# BT-2.net
KiCad netlist of a schematic drawn in EAGLE
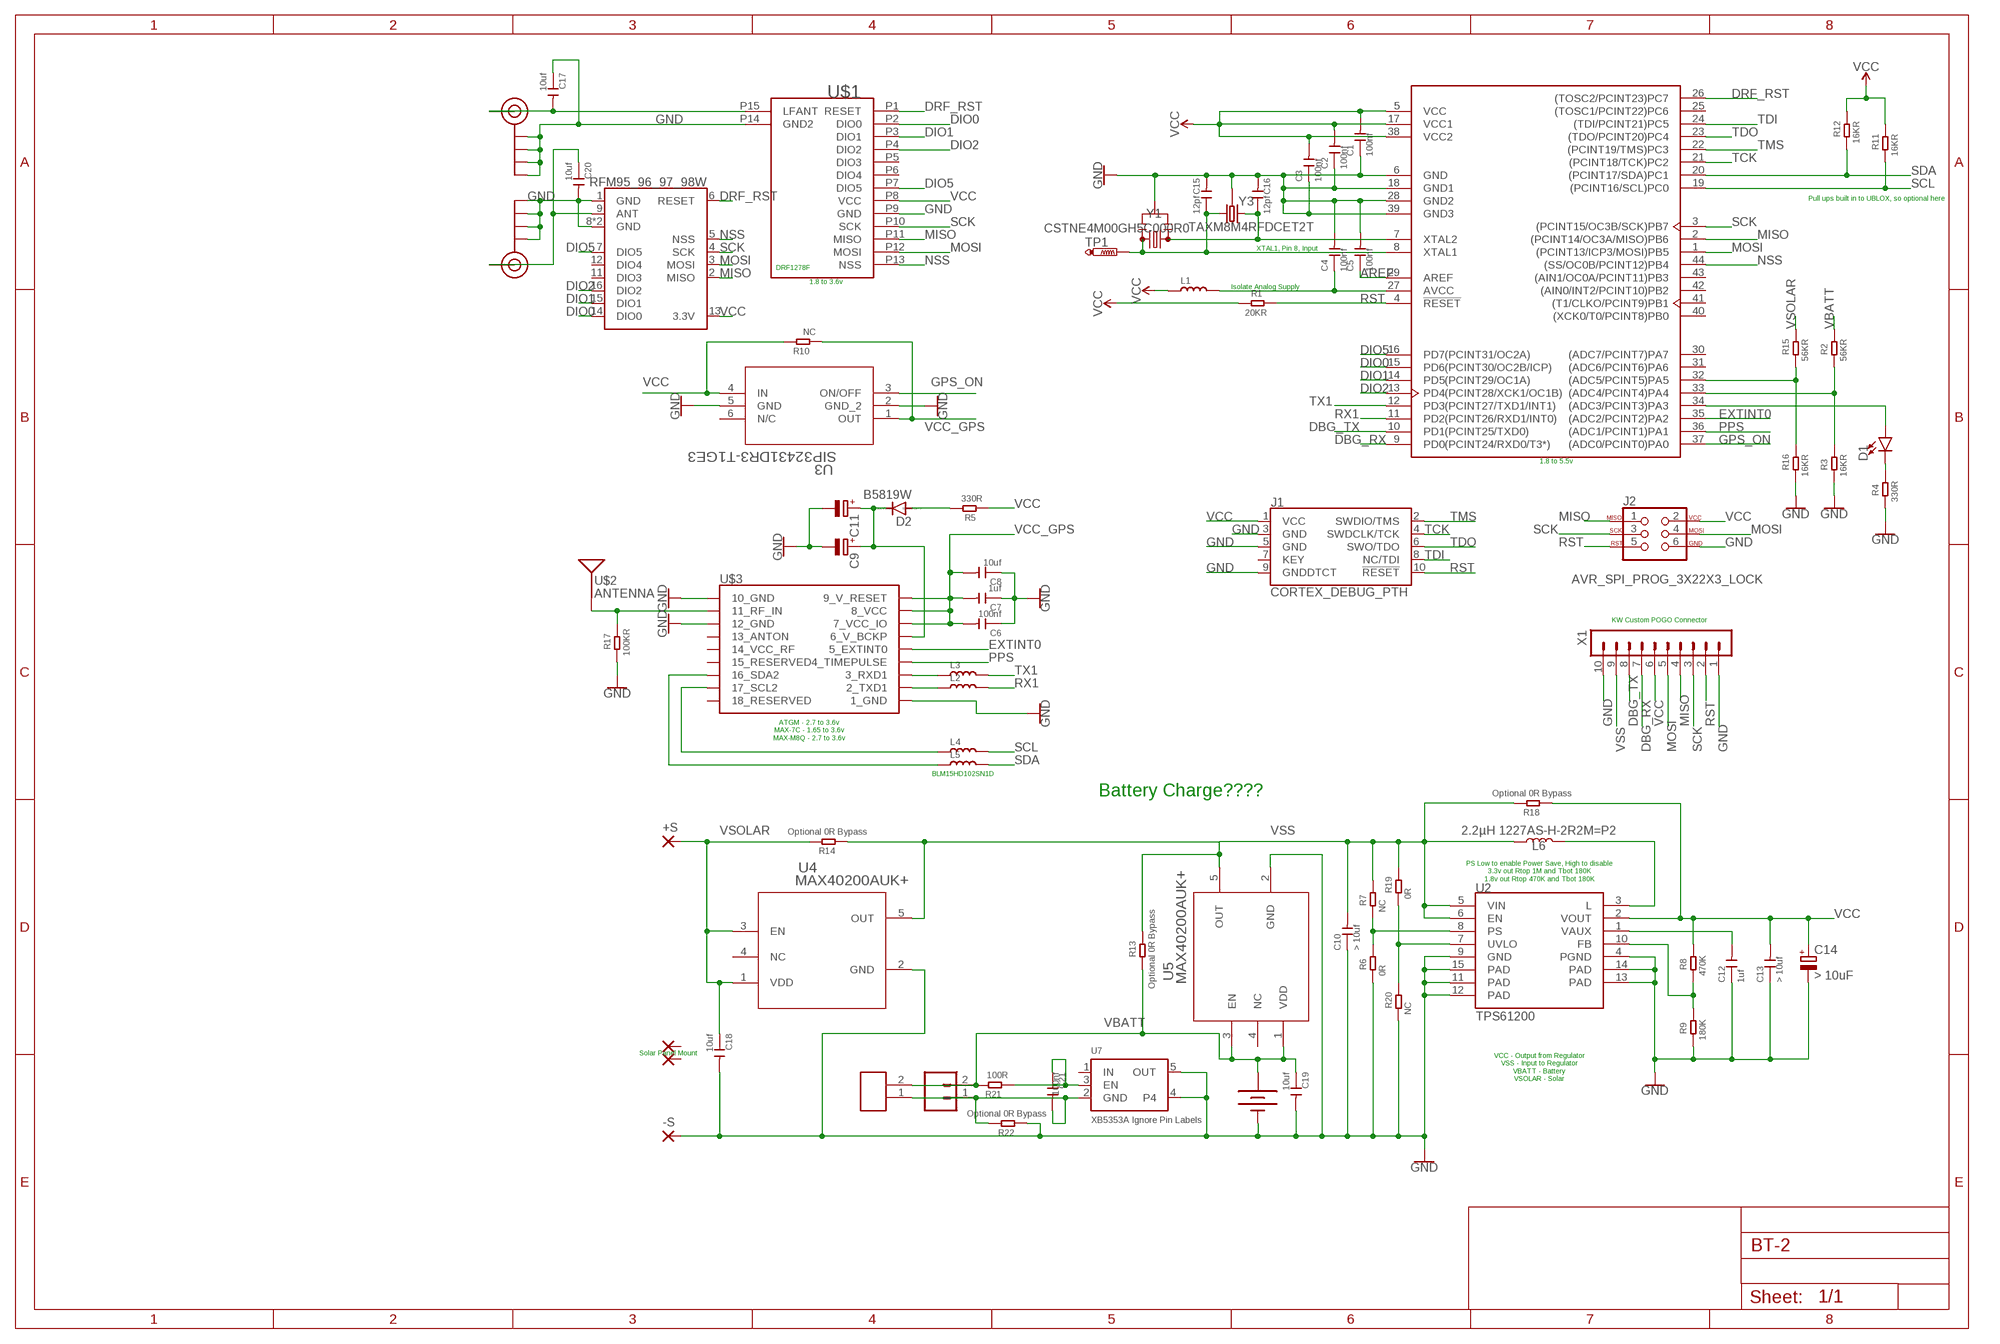
[diagram p0: schematic, sheet 1]

(export (version "E")
  (design (tool "Eeschema 10.0.6"))
  (components
    (comp (ref "+S")
      (value "SMD2")
      (footprint "eagle-import:SMD1,27-2,54")
      (libsource (lib "eagle-import") (part "SMD2"))
    )
    (comp (ref "-S")
      (value "SMD2")
      (footprint "eagle-import:SMD1,27-2,54")
      (libsource (lib "eagle-import") (part "SMD2"))
    )
    (comp (ref "BT1")
      (value "BATTERY")
      (footprint "eagle-import:BATTERY-AA-AAA")
      (libsource (lib "eagle-import") (part "BATTERY"))
    )
    (comp (ref "C1")
      (value "100nf")
      (footprint "eagle-import:C0402")
      (fields (field (name "MPN") "CC0402KRX7R8BB104"))
      (libsource (lib "eagle-import") (part "CERAMIC-100NF-25V-10%-X7R(0402)"))
    )
    (comp (ref "C2")
      (value "100nf")
      (footprint "eagle-import:C0402")
      (fields (field (name "MPN") "CC0402KRX7R8BB104"))
      (libsource (lib "eagle-import") (part "CERAMIC-100NF-25V-10%-X7R(0402)"))
    )
    (comp (ref "C3")
      (value "100nf")
      (footprint "eagle-import:C0402")
      (fields (field (name "MPN") "CC0402KRX7R8BB104"))
      (libsource (lib "eagle-import") (part "CERAMIC-100NF-25V-10%-X7R(0402)"))
    )
    (comp (ref "C4")
      (value "100nf")
      (footprint "eagle-import:C0402")
      (fields (field (name "MPN") "CC0402KRX7R8BB104"))
      (libsource (lib "eagle-import") (part "CERAMIC-100NF-25V-10%-X7R(0402)"))
    )
    (comp (ref "C5")
      (value "100nf")
      (footprint "eagle-import:C0402")
      (fields (field (name "MPN") "CC0402KRX7R8BB104"))
      (libsource (lib "eagle-import") (part "CERAMIC-100NF-25V-10%-X7R(0402)"))
    )
    (comp (ref "C6")
      (value "100nf")
      (footprint "eagle-import:C0402")
      (fields (field (name "MPN") "CC0402KRX7R8BB104"))
      (libsource (lib "eagle-import") (part "CERAMIC-100NF-25V-10%-X7R(0402)"))
    )
    (comp (ref "C7")
      (value "1uf")
      (footprint "eagle-import:C0402")
      (fields (field (name "MPN") "CC0402KRX5R6BB105"))
      (libsource (lib "eagle-import") (part "CERAMIC-1UF-10V-10%-X5R(0402)"))
    )
    (comp (ref "C8")
      (value "10uf")
      (footprint "eagle-import:C0402")
      (fields (field (name "MPN") "CC0402MRX5R5BB106"))
      (libsource (lib "eagle-import") (part "CERAMIC-10UF-6.3V-20%-X5R(0402)"))
    )
    (comp (ref "C9")
      (value "RCL_CPOL-EUSMCC")
      (footprint "eagle-import:RCL_SMC_C")
      (libsource (lib "eagle-import") (part "RCL_CPOL-EUSMCC"))
    )
    (comp (ref "C10")
      (value "> 10uf")
      (footprint "eagle-import:C0603")
      (fields (field (name "MPN") "CC0603KRX5R6BB106"))
      (libsource (lib "eagle-import") (part "CERAMIC-10UF-10V-10%-X5R(0603)"))
    )
    (comp (ref "C11")
      (value "C-POL_ECAP-10.5MM")
      (footprint "eagle-import:CAPAE1030X1050N")
      (libsource (lib "eagle-import") (part "C-POLECAP-10.5MM_"))
    )
    (comp (ref "C12")
      (value "1uf")
      (footprint "eagle-import:C0402")
      (fields (field (name "MPN") "CC0402KRX5R6BB105"))
      (libsource (lib "eagle-import") (part "CERAMIC-1UF-10V-10%-X5R(0402)"))
    )
    (comp (ref "C13")
      (value "> 10uf")
      (footprint "eagle-import:C0603")
      (fields (field (name "MPN") "CC0603KRX5R6BB106"))
      (libsource (lib "eagle-import") (part "CERAMIC-10UF-10V-10%-X5R(0603)"))
    )
    (comp (ref "C14")
      (value "> 10uF")
      (footprint "eagle-import:RCL_SMC_C")
      (libsource (lib "eagle-import") (part "RCL_CPOL-EUSMCC"))
    )
    (comp (ref "C15")
      (value "12pf")
      (footprint "eagle-import:C0402")
      (fields (field (name "MPN") "CC0402KRX7R8BB104"))
      (libsource (lib "eagle-import") (part "CERAMIC-100NF-25V-10%-X7R(0402)"))
    )
    (comp (ref "C16")
      (value "12pf")
      (footprint "eagle-import:C0402")
      (fields (field (name "MPN") "CC0402KRX7R8BB104"))
      (libsource (lib "eagle-import") (part "CERAMIC-100NF-25V-10%-X7R(0402)"))
    )
    (comp (ref "C17")
      (value "10uf")
      (footprint "eagle-import:C0402")
      (fields (field (name "MPN") "CC0402MRX5R5BB106"))
      (libsource (lib "eagle-import") (part "CERAMIC-10UF-6.3V-20%-X5R(0402)"))
    )
    (comp (ref "C18")
      (value "10uf")
      (footprint "eagle-import:C0402")
      (fields (field (name "MPN") "CC0402MRX5R5BB106"))
      (libsource (lib "eagle-import") (part "CERAMIC-10UF-6.3V-20%-X5R(0402)"))
    )
    (comp (ref "C19")
      (value "10uf")
      (footprint "eagle-import:C0402")
      (fields (field (name "MPN") "CC0402MRX5R5BB106"))
      (libsource (lib "eagle-import") (part "CERAMIC-10UF-6.3V-20%-X5R(0402)"))
    )
    (comp (ref "C20")
      (value "10uf")
      (footprint "eagle-import:C0402")
      (fields (field (name "MPN") "CC0402MRX5R5BB106"))
      (libsource (lib "eagle-import") (part "CERAMIC-10UF-6.3V-20%-X5R(0402)"))
    )
    (comp (ref "C21")
      (value "100nf")
      (footprint "eagle-import:C0402")
      (fields (field (name "MPN") "CC0402KRX7R8BB104"))
      (libsource (lib "eagle-import") (part "CERAMIC-100NF-25V-10%-X7R(0402)"))
    )
    (comp (ref "D1")
      (value "LED0603")
      (footprint "eagle-import:LED-0603")
      (libsource (lib "eagle-import") (part "LED0603"))
    )
    (comp (ref "D2")
      (value "B5819W")
      (footprint "eagle-import:SOD123")
      (libsource (lib "eagle-import") (part "DIODE-SOD123"))
    )
    (comp (ref "J$1")
      (value "SMA_EDGE")
      (footprint "eagle-import:SMA-EDGE")
      (libsource (lib "eagle-import") (part "SMA_EDGE"))
    )
    (comp (ref "J$2")
      (value "SMA_EDGE")
      (footprint "eagle-import:SMA-EDGE")
      (libsource (lib "eagle-import") (part "SMA_EDGE"))
    )
    (comp (ref "J1")
      (value "CORTEX_DEBUG_PTH")
      (footprint "eagle-import:2X5-PTH-1.27MM")
      (libsource (lib "eagle-import") (part "CORTEX_DEBUG_PTH"))
    )
    (comp (ref "J2")
      (value "AVR_SPI_PROG_3X22X3_LOCK")
      (footprint "eagle-import:2X3_LOCK")
      (libsource (lib "eagle-import") (part "AVR_SPI_PROG_3X22X3_LOCK"))
    )
    (comp (ref "J3")
      (value "JST_ZH_2PIN")
      (footprint "eagle-import:JST_ZH_2PIN")
      (libsource (lib "eagle-import") (part "JST_ZH_2PIN"))
    )
    (comp (ref "J4")
      (value "CONN_02JST-PTH-2-KIT")
      (footprint "eagle-import:JST-2-PTH-KIT")
      (libsource (lib "eagle-import") (part "CONN_02JST-PTH-2-KIT"))
    )
    (comp (ref "L1")
      (value "BLM15HD102SN1D")
      (footprint "eagle-import:L0402")
      (libsource (lib "eagle-import") (part "SMD-INDUCTOR-3.3NH-0.3NH-300MA(0402)"))
    )
    (comp (ref "L2")
      (value "BLM15HD102SN1D")
      (footprint "eagle-import:L0402")
      (libsource (lib "eagle-import") (part "SMD-INDUCTOR-3.3NH-0.3NH-300MA(0402)"))
    )
    (comp (ref "L3")
      (value "BLM15HD102SN1D")
      (footprint "eagle-import:L0402")
      (libsource (lib "eagle-import") (part "SMD-INDUCTOR-3.3NH-0.3NH-300MA(0402)"))
    )
    (comp (ref "L4")
      (value "BLM15HD102SN1D")
      (footprint "eagle-import:L0402")
      (libsource (lib "eagle-import") (part "SMD-INDUCTOR-3.3NH-0.3NH-300MA(0402)"))
    )
    (comp (ref "L5")
      (value "BLM15HD102SN1D")
      (footprint "eagle-import:L0402")
      (libsource (lib "eagle-import") (part "SMD-INDUCTOR-3.3NH-0.3NH-300MA(0402)"))
    )
    (comp (ref "L6")
      (value "2.2µH 1227AS-H-2R2M=P2")
      (footprint "eagle-import:INDUCTOR_4.7UH")
      (libsource (lib "eagle-import") (part "INDUCTOR-CDRH-4.7UH"))
    )
    (comp (ref "NC1")
      (value "SMD2")
      (footprint "eagle-import:SMD1,27-2,54")
      (libsource (lib "eagle-import") (part "SMD2"))
    )
    (comp (ref "NC2")
      (value "SMD2")
      (footprint "eagle-import:SMD1,27-2,54")
      (libsource (lib "eagle-import") (part "SMD2"))
    )
    (comp (ref "R1")
      (value "20KR")
      (footprint "eagle-import:R0402")
      (fields (field (name "MPN") "RC0402JR-070RL"))
      (libsource (lib "eagle-import") (part "SMD-RES-20K-5%-1/16W(0402)"))
    )
    (comp (ref "R2")
      (value "56KR")
      (footprint "eagle-import:R0402")
      (fields (field (name "MPN") "RC0402JR-070RL"))
      (libsource (lib "eagle-import") (part "SMD-RES-20K-5%-1/16W(0402)"))
    )
    (comp (ref "R3")
      (value "16KR")
      (footprint "eagle-import:R0402")
      (fields (field (name "MPN") "RC0402JR-070RL"))
      (libsource (lib "eagle-import") (part "SMD-RES-20K-5%-1/16W(0402)"))
    )
    (comp (ref "R4")
      (value "330R")
      (footprint "eagle-import:R0402")
      (fields (field (name "MPN") "RC0402JR-070RL"))
      (libsource (lib "eagle-import") (part "SMD-RES-20K-5%-1/16W(0402)"))
    )
    (comp (ref "R5")
      (value "330R")
      (footprint "eagle-import:R0402")
      (fields (field (name "MPN") "RC0402JR-070RL"))
      (libsource (lib "eagle-import") (part "SMD-RES-20K-5%-1/16W(0402)"))
    )
    (comp (ref "R6")
      (value "0R")
      (footprint "eagle-import:R0402")
      (fields (field (name "MPN") "RC0402JR-070RL"))
      (libsource (lib "eagle-import") (part "SMD-RES-20K-5%-1/16W(0402)"))
    )
    (comp (ref "R7")
      (value "NC")
      (footprint "eagle-import:R0402")
      (fields (field (name "MPN") "RC0402JR-070RL"))
      (libsource (lib "eagle-import") (part "SMD-RES-20K-5%-1/16W(0402)"))
    )
    (comp (ref "R8")
      (value "470K")
      (footprint "eagle-import:R0402")
      (fields (field (name "MPN") "RC0402JR-070RL"))
      (libsource (lib "eagle-import") (part "SMD-RES-20K-5%-1/16W(0402)"))
    )
    (comp (ref "R9")
      (value "180K")
      (footprint "eagle-import:R0402")
      (fields (field (name "MPN") "RC0402JR-070RL"))
      (libsource (lib "eagle-import") (part "SMD-RES-20K-5%-1/16W(0402)"))
    )
    (comp (ref "R10")
      (value "NC")
      (footprint "eagle-import:R0402")
      (fields (field (name "MPN") "RC0402JR-070RL"))
      (libsource (lib "eagle-import") (part "SMD-RES-20K-5%-1/16W(0402)"))
    )
    (comp (ref "R11")
      (value "16KR")
      (footprint "eagle-import:R0402")
      (fields (field (name "MPN") "RC0402JR-070RL"))
      (libsource (lib "eagle-import") (part "SMD-RES-20K-5%-1/16W(0402)"))
    )
    (comp (ref "R12")
      (value "16KR")
      (footprint "eagle-import:R0402")
      (fields (field (name "MPN") "RC0402JR-070RL"))
      (libsource (lib "eagle-import") (part "SMD-RES-20K-5%-1/16W(0402)"))
    )
    (comp (ref "R13")
      (value "Optional 0R Bypass")
      (footprint "eagle-import:R0402")
      (fields (field (name "MPN") "RC0402JR-070RL"))
      (libsource (lib "eagle-import") (part "SMD-RES-20K-5%-1/16W(0402)"))
    )
    (comp (ref "R14")
      (value "Optional 0R Bypass")
      (footprint "eagle-import:R0402")
      (fields (field (name "MPN") "RC0402JR-070RL"))
      (libsource (lib "eagle-import") (part "SMD-RES-20K-5%-1/16W(0402)"))
    )
    (comp (ref "R15")
      (value "56KR")
      (footprint "eagle-import:R0402")
      (fields (field (name "MPN") "RC0402JR-070RL"))
      (libsource (lib "eagle-import") (part "SMD-RES-20K-5%-1/16W(0402)"))
    )
    (comp (ref "R16")
      (value "16KR")
      (footprint "eagle-import:R0402")
      (fields (field (name "MPN") "RC0402JR-070RL"))
      (libsource (lib "eagle-import") (part "SMD-RES-20K-5%-1/16W(0402)"))
    )
    (comp (ref "R17")
      (value "100KR")
      (footprint "eagle-import:R0402")
      (fields (field (name "MPN") "RC0402JR-070RL"))
      (libsource (lib "eagle-import") (part "SMD-RES-20K-5%-1/16W(0402)"))
    )
    (comp (ref "R18")
      (value "Optional 0R Bypass")
      (footprint "eagle-import:R0402")
      (fields (field (name "MPN") "RC0402JR-070RL"))
      (libsource (lib "eagle-import") (part "SMD-RES-20K-5%-1/16W(0402)"))
    )
    (comp (ref "R19")
      (value "0R")
      (footprint "eagle-import:R0402")
      (fields (field (name "MPN") "RC0402JR-070RL"))
      (libsource (lib "eagle-import") (part "SMD-RES-20K-5%-1/16W(0402)"))
    )
    (comp (ref "R20")
      (value "NC")
      (footprint "eagle-import:R0402")
      (fields (field (name "MPN") "RC0402JR-070RL"))
      (libsource (lib "eagle-import") (part "SMD-RES-20K-5%-1/16W(0402)"))
    )
    (comp (ref "R21")
      (value "100R")
      (footprint "eagle-import:R0402")
      (fields (field (name "MPN") "RC0402JR-070RL"))
      (libsource (lib "eagle-import") (part "SMD-RES-20K-5%-1/16W(0402)"))
    )
    (comp (ref "R22")
      (value "Optional 0R Bypass")
      (footprint "eagle-import:R0402")
      (fields (field (name "MPN") "RC0402JR-070RL"))
      (libsource (lib "eagle-import") (part "SMD-RES-20K-5%-1/16W(0402)"))
    )
    (comp (ref "TP1")
      (value "TESTPAD_PTR1TP10R")
      (footprint "eagle-import:TESTPAD_TP10R")
      (libsource (lib "eagle-import") (part "TESTPAD_PTR1TP10R"))
    )
    (comp (ref "U$1")
      (value "DRF1278F_2NO_PINS")
      (footprint "eagle-import:DRF1278F_2_NO_PINS")
      (libsource (lib "eagle-import") (part "DRF1278F_2NO_PINS"))
    )
    (comp (ref "U$2")
      (value "ANTENNA")
      (footprint "eagle-import:ANT-GPS-3X10MM")
      (libsource (lib "eagle-import") (part "ANTENNA"))
    )
    (comp (ref "U$3")
      (value "AVA_UBLOX_MAX-6")
      (footprint "eagle-import:AVA_UBLOX_MAX-6")
      (libsource (lib "eagle-import") (part "AVA_UBLOX_MAX-6"))
    )
    (comp (ref "U1")
      (value "ATMEGA1284P-AU")
      (footprint "eagle-import:TQFP-44")
      (fields
        (field (name "DIGIKEY_PART_NUMBER") "ATMEGA1284P-AU-ND")
        (field (name "MANUFACTURER") "Microchip Technology")
        (field (name "CREATED_BY") "PCBLayout.com")
      )
      (libsource (lib "eagle-import") (part "ATMEGA1284P-AU"))
    )
    (comp (ref "U2")
      (value "TPS61200")
      (footprint "eagle-import:QFN-10_PAD")
      (libsource (lib "eagle-import") (part "TPS61200"))
    )
    (comp (ref "U3")
      (value "SIP32431DR3-T1GE3")
      (footprint "eagle-import:SC-70-6_VIS")
      (fields (field (name "COPYRIGHT") "Copyright (C) 2018 Accelerated Designs. All rights reserved"))
      (libsource (lib "eagle-import") (part "SIP32431DR3-T1GE3"))
    )
    (comp (ref "U4")
      (value "MAX40200AUK+")
      (footprint "eagle-import:RAJX_V4.5_REVA_21-0057F_MXM")
      (fields (field (name "COPYRIGHT") "Copyright (C) 2018 Accelerated Designs. All rights reserved"))
      (libsource (lib "eagle-import") (part "RAJX_V4.5_REVA_MAX40200AUK+"))
    )
    (comp (ref "U5")
      (value "MAX40200AUK+")
      (footprint "eagle-import:RAJX_V4.5_REVA_21-0057F_MXM")
      (fields (field (name "COPYRIGHT") "Copyright (C) 2018 Accelerated Designs. All rights reserved"))
      (libsource (lib "eagle-import") (part "RAJX_V4.5_REVA_MAX40200AUK+"))
    )
    (comp (ref "U6")
      (value "RFM95_96_97_98W")
      (footprint "eagle-import:RFM69HCW-XXXS2")
      (libsource (lib "eagle-import") (part "RFM69HCW-433"))
    )
    (comp (ref "U7")
      (value "XB5353A Ignore Pin Labels")
      (footprint "eagle-import:SOT23-5_1")
      (libsource (lib "eagle-import") (part "VREG_SOT23-5"))
    )
    (comp (ref "X1")
      (value "KEW_HF_V13_M_1R10KW_50MIL-H")
      (footprint "eagle-import:KEW_HF_V13_M_1R09_50MIL-H")
      (libsource (lib "eagle-import") (part "KEW_HF_V13_M_1R10KW_50MIL-H"))
    )
    (comp (ref "Y1")
      (value "CSTNE4M00GH5C000R0")
      (footprint "eagle-import:SPARKFUN-CLOCKS-KW_RESONATOR-SMD-3.2X1.3")
      (libsource (lib "eagle-import") (part "SPARKFUN-CLOCKS-KW_RESONATOR-8MHZSMD_3.2X1.3"))
    )
    (comp (ref "Y3")
      (value "TAXM8M4RFDCET2T")
      (footprint "eagle-import:CRYSTAL-SMD-3.2X2.5MM")
      (libsource (lib "eagle-import") (part "CRYSTAL-GROUNDEDSMD-3.2X2.5"))
    )
  )
  (nets
    (net (code "1") (name "/AREF") (class "Default")
      (node (ref "C5") (pin "1") (pinfunction "1_1") (pintype "passive"))
      (node (ref "U1") (pin "29") (pinfunction "AREF_29") (pintype "input"))
    )
    (net (code "2") (name "/DBG_RX") (class "Default")
      (node (ref "U1") (pin "9") (pinfunction "PD0(PCINT24/RXD0/T3*)_9") (pintype "bidirectional"))
      (node (ref "X1") (pin "7") (pinfunction "7_7") (pintype "bidirectional"))
    )
    (net (code "3") (name "/DBG_TX") (class "Default")
      (node (ref "U1") (pin "10") (pinfunction "PD1(PCINT25/TXD0)_10") (pintype "bidirectional"))
      (node (ref "X1") (pin "8") (pinfunction "8_8") (pintype "bidirectional"))
    )
    (net (code "4") (name "/DIO0") (class "Default")
      (node (ref "U$1") (pin "P2") (pinfunction "DIO0_P2") (pintype "bidirectional"))
      (node (ref "U1") (pin "15") (pinfunction "PD6(PCINT30/OC2B/ICP)_15") (pintype "bidirectional"))
      (node (ref "U6") (pin "14") (pinfunction "DIO0_14") (pintype "bidirectional"))
    )
    (net (code "5") (name "/DIO1") (class "Default")
      (node (ref "U$1") (pin "P3") (pinfunction "DIO1_P3") (pintype "bidirectional"))
      (node (ref "U1") (pin "14") (pinfunction "PD5(PCINT29/OC1A)_14") (pintype "bidirectional"))
      (node (ref "U6") (pin "15") (pinfunction "DIO1_15") (pintype "bidirectional"))
    )
    (net (code "6") (name "/DIO2") (class "Default")
      (node (ref "U$1") (pin "P4") (pinfunction "DIO2_P4") (pintype "bidirectional"))
      (node (ref "U1") (pin "13") (pinfunction "PD4(PCINT28/XCK1/OC1B)_13") (pintype "bidirectional"))
      (node (ref "U6") (pin "16") (pinfunction "DIO2_16") (pintype "bidirectional"))
    )
    (net (code "7") (name "/DIO5") (class "Default")
      (node (ref "U$1") (pin "P7") (pinfunction "DIO5_P7") (pintype "bidirectional"))
      (node (ref "U1") (pin "16") (pinfunction "PD7(PCINT31/OC2A)_16") (pintype "bidirectional"))
      (node (ref "U6") (pin "7") (pinfunction "DIO5_7") (pintype "bidirectional"))
    )
    (net (code "8") (name "/DRF_RST") (class "Default")
      (node (ref "U$1") (pin "P1") (pinfunction "RESET_P1") (pintype "bidirectional"))
      (node (ref "U1") (pin "26") (pinfunction "(TOSC2/PCINT23)PC7_26") (pintype "bidirectional"))
      (node (ref "U6") (pin "6") (pinfunction "RESET_6") (pintype "input"))
    )
    (net (code "9") (name "/EXTINT0") (class "Default")
      (node (ref "U$3") (pin "5_EXTINT0") (pinfunction "5_EXTINT0_5_EXTINT0") (pintype "bidirectional"))
      (node (ref "U1") (pin "35") (pinfunction "(ADC2/PCINT2)PA2_35") (pintype "bidirectional"))
    )
    (net (code "10") (name "/GPS_ON") (class "Default")
      (node (ref "U1") (pin "37") (pinfunction "(ADC0/PCINT0)PA0_37") (pintype "bidirectional"))
      (node (ref "U3") (pin "3") (pinfunction "ON/OFF_3") (pintype "passive"))
    )
    (net (code "11") (name "/IN") (class "Default")
      (node (ref "U7") (pin "1") (pinfunction "IN_1") (pintype "power_in"))
    )
    (net (code "12") (name "/MISO") (class "Default")
      (node (ref "J2") (pin "1") (pinfunction "1_1") (pintype "passive"))
      (node (ref "U$1") (pin "P11") (pinfunction "MISO_P11") (pintype "bidirectional"))
      (node (ref "U1") (pin "2") (pinfunction "(PCINT14/OC3A/MISO)PB6_2") (pintype "bidirectional"))
      (node (ref "U6") (pin "2") (pinfunction "MISO_2") (pintype "bidirectional"))
      (node (ref "X1") (pin "4") (pinfunction "4_4") (pintype "bidirectional"))
    )
    (net (code "13") (name "/MOSI") (class "Default")
      (node (ref "J2") (pin "4") (pinfunction "4_4") (pintype "passive"))
      (node (ref "U$1") (pin "P12") (pinfunction "MOSI_P12") (pintype "bidirectional"))
      (node (ref "U1") (pin "1") (pinfunction "(PCINT13/ICP3/MOSI)PB5_1") (pintype "bidirectional"))
      (node (ref "U6") (pin "3") (pinfunction "MOSI_3") (pintype "input"))
      (node (ref "X1") (pin "5") (pinfunction "5_5") (pintype "bidirectional"))
    )
    (net (code "14") (name "/NSS") (class "Default")
      (node (ref "U$1") (pin "P13") (pinfunction "NSS_P13") (pintype "bidirectional"))
      (node (ref "U1") (pin "44") (pinfunction "(SS/OC0B/PCINT12)PB4_44") (pintype "bidirectional"))
      (node (ref "U6") (pin "5") (pinfunction "NSS_5") (pintype "input"))
    )
    (net (code "15") (name "/PPS") (class "Default")
      (node (ref "U$3") (pin "4_TIMEPULSE") (pinfunction "4_TIMEPULSE_4_TIMEPULSE") (pintype "bidirectional"))
      (node (ref "U1") (pin "36") (pinfunction "(ADC1/PCINT1)PA1_36") (pintype "bidirectional"))
    )
    (net (code "16") (name "/RST") (class "Default")
      (node (ref "J1") (pin "10") (pinfunction "~{RESET}_10") (pintype "bidirectional"))
      (node (ref "J2") (pin "5") (pinfunction "5_5") (pintype "passive"))
      (node (ref "R1") (pin "2") (pinfunction "2_2") (pintype "passive"))
      (node (ref "U1") (pin "4") (pinfunction "~{RESET}_4") (pintype "input"))
      (node (ref "X1") (pin "2") (pinfunction "2_2") (pintype "bidirectional"))
    )
    (net (code "17") (name "/RX1") (class "Default")
      (node (ref "L2") (pin "2") (pinfunction "2_2") (pintype "passive"))
      (node (ref "U1") (pin "11") (pinfunction "PD2(PCINT26/RXD1/INT0)_11") (pintype "bidirectional"))
    )
    (net (code "18") (name "/SCK") (class "Default")
      (node (ref "J2") (pin "3") (pinfunction "3_3") (pintype "passive"))
      (node (ref "U$1") (pin "P10") (pinfunction "SCK_P10") (pintype "bidirectional"))
      (node (ref "U1") (pin "3") (pinfunction "(PCINT15/OC3B/SCK)PB7_3") (pintype "bidirectional"))
      (node (ref "U6") (pin "4") (pinfunction "SCK_4") (pintype "input"))
      (node (ref "X1") (pin "3") (pinfunction "3_3") (pintype "bidirectional"))
    )
    (net (code "19") (name "/SCL") (class "Default")
      (node (ref "L4") (pin "2") (pinfunction "2_2") (pintype "passive"))
      (node (ref "R11") (pin "1") (pinfunction "1_1") (pintype "passive"))
      (node (ref "U1") (pin "19") (pinfunction "(PCINT16/SCL)PC0_19") (pintype "bidirectional"))
    )
    (net (code "20") (name "/SDA") (class "Default")
      (node (ref "L5") (pin "2") (pinfunction "2_2") (pintype "passive"))
      (node (ref "R12") (pin "1") (pinfunction "1_1") (pintype "passive"))
      (node (ref "U1") (pin "20") (pinfunction "(PCINT17/SDA)PC1_20") (pintype "bidirectional"))
    )
    (net (code "21") (name "/TCK") (class "Default")
      (node (ref "J1") (pin "4") (pinfunction "SWDCLK/TCK_4") (pintype "bidirectional"))
      (node (ref "U1") (pin "21") (pinfunction "(PCINT18/TCK)PC2_21") (pintype "bidirectional"))
    )
    (net (code "22") (name "/TDI") (class "Default")
      (node (ref "J1") (pin "8") (pinfunction "NC/TDI_8") (pintype "bidirectional"))
      (node (ref "U1") (pin "24") (pinfunction "(TDI/PCINT21)PC5_24") (pintype "bidirectional"))
    )
    (net (code "23") (name "/TDO") (class "Default")
      (node (ref "J1") (pin "6") (pinfunction "SWO/TDO_6") (pintype "bidirectional"))
      (node (ref "U1") (pin "23") (pinfunction "(TDO/PCINT20)PC4_23") (pintype "bidirectional"))
    )
    (net (code "24") (name "/TMS") (class "Default")
      (node (ref "J1") (pin "2") (pinfunction "SWDIO/TMS_2") (pintype "bidirectional"))
      (node (ref "U1") (pin "22") (pinfunction "(PCINT19/TMS)PC3_22") (pintype "bidirectional"))
    )
    (net (code "25") (name "/TX1") (class "Default")
      (node (ref "L3") (pin "2") (pinfunction "2_2") (pintype "passive"))
      (node (ref "U1") (pin "12") (pinfunction "PD3(PCINT27/TXD1/INT1)_12") (pintype "bidirectional"))
    )
    (net (code "26") (name "/VBATT") (class "Default")
      (node (ref "BT1") (pin "P$1") (pinfunction "+_P$1") (pintype "power_in"))
      (node (ref "BT1") (pin "P$3") (pinfunction "+_P$3") (pintype "power_in"))
      (node (ref "BT1") (pin "P$5") (pinfunction "+_P$5") (pintype "power_in"))
      (node (ref "BT1") (pin "P$6") (pinfunction "+_P$6") (pintype "power_in"))
      (node (ref "C19") (pin "1") (pinfunction "1_1") (pintype "passive"))
      (node (ref "J3") (pin "2") (pinfunction "P$2_2") (pintype "bidirectional"))
      (node (ref "J4") (pin "2") (pinfunction "2_2") (pintype "passive"))
      (node (ref "R13") (pin "1") (pinfunction "1_1") (pintype "passive"))
      (node (ref "R2") (pin "2") (pinfunction "2_2") (pintype "passive"))
      (node (ref "R21") (pin "2") (pinfunction "2_2") (pintype "passive"))
      (node (ref "U5") (pin "1") (pinfunction "VDD_1") (pintype "power_in"))
      (node (ref "U5") (pin "3") (pinfunction "EN_3") (pintype "passive"))
    )
    (net (code "27") (name "/VCC_GPS") (class "Default")
      (node (ref "C6") (pin "2") (pinfunction "2_2") (pintype "passive"))
      (node (ref "C7") (pin "2") (pinfunction "2_2") (pintype "passive"))
      (node (ref "C8") (pin "2") (pinfunction "2_2") (pintype "passive"))
      (node (ref "R10") (pin "1") (pinfunction "1_1") (pintype "passive"))
      (node (ref "U$3") (pin "7_VCC_IO") (pinfunction "7_VCC_IO_7_VCC_IO") (pintype "power_in"))
      (node (ref "U$3") (pin "8_VCC") (pinfunction "8_VCC_8_VCC") (pintype "power_in"))
      (node (ref "U$3") (pin "9_V_RESET") (pinfunction "9_V_RESET_9_V_RESET") (pintype "power_in"))
      (node (ref "U3") (pin "1") (pinfunction "OUT_1") (pintype "output"))
    )
    (net (code "28") (name "/VSOLAR") (class "Default")
      (node (ref "+S") (pin "1") (pinfunction "P_1") (pintype "passive"))
      (node (ref "C18") (pin "1") (pinfunction "1_1") (pintype "passive"))
      (node (ref "R14") (pin "2") (pinfunction "2_2") (pintype "passive"))
      (node (ref "R15") (pin "2") (pinfunction "2_2") (pintype "passive"))
      (node (ref "U4") (pin "1") (pinfunction "VDD_1") (pintype "power_in"))
      (node (ref "U4") (pin "3") (pinfunction "EN_3") (pintype "passive"))
    )
    (net (code "29") (name "/VSS") (class "Default")
      (node (ref "C10") (pin "2") (pinfunction "2_2") (pintype "passive"))
      (node (ref "L6") (pin "P$1") (pinfunction "1_P$1") (pintype "passive"))
      (node (ref "R13") (pin "2") (pinfunction "2_2") (pintype "passive"))
      (node (ref "R14") (pin "1") (pinfunction "1_1") (pintype "passive"))
      (node (ref "R18") (pin "2") (pinfunction "2_2") (pintype "passive"))
      (node (ref "R19") (pin "2") (pinfunction "2_2") (pintype "passive"))
      (node (ref "R7") (pin "2") (pinfunction "2_2") (pintype "passive"))
      (node (ref "U2") (pin "5") (pinfunction "VIN_5") (pintype "power_in"))
      (node (ref "U2") (pin "6") (pinfunction "EN_6") (pintype "input"))
      (node (ref "U4") (pin "5") (pinfunction "OUT_5") (pintype "output"))
      (node (ref "U5") (pin "5") (pinfunction "OUT_5") (pintype "output"))
      (node (ref "X1") (pin "9") (pinfunction "9_9") (pintype "bidirectional"))
    )
    (net (code "30") (name "GND") (class "Default")
      (node (ref "-S") (pin "1") (pinfunction "P_1") (pintype "passive"))
      (node (ref "BT1") (pin "P$2") (pinfunction "-_P$2") (pintype "power_in"))
      (node (ref "BT1") (pin "P$4") (pinfunction "-_P$4") (pintype "power_in"))
      (node (ref "BT1") (pin "P$7") (pinfunction "-_P$7") (pintype "power_in"))
      (node (ref "BT1") (pin "P$8") (pinfunction "-_P$8") (pintype "power_in"))
      (node (ref "C1") (pin "1") (pinfunction "1_1") (pintype "passive"))
      (node (ref "C10") (pin "1") (pinfunction "1_1") (pintype "passive"))
      (node (ref "C11") (pin "2") (pinfunction "-_2") (pintype "passive"))
      (node (ref "C12") (pin "1") (pinfunction "1_1") (pintype "passive"))
      (node (ref "C13") (pin "1") (pinfunction "1_1") (pintype "passive"))
      (node (ref "C14") (pin "-") (pinfunction "-_-") (pintype "passive"))
      (node (ref "C15") (pin "2") (pinfunction "2_2") (pintype "passive"))
      (node (ref "C16") (pin "2") (pinfunction "2_2") (pintype "passive"))
      (node (ref "C17") (pin "1") (pinfunction "1_1") (pintype "passive"))
      (node (ref "C18") (pin "2") (pinfunction "2_2") (pintype "passive"))
      (node (ref "C19") (pin "2") (pinfunction "2_2") (pintype "passive"))
      (node (ref "C2") (pin "1") (pinfunction "1_1") (pintype "passive"))
      (node (ref "C20") (pin "2") (pinfunction "2_2") (pintype "passive"))
      (node (ref "C3") (pin "1") (pinfunction "1_1") (pintype "passive"))
      (node (ref "C4") (pin "2") (pinfunction "2_2") (pintype "passive"))
      (node (ref "C5") (pin "2") (pinfunction "2_2") (pintype "passive"))
      (node (ref "C6") (pin "1") (pinfunction "1_1") (pintype "passive"))
      (node (ref "C7") (pin "1") (pinfunction "1_1") (pintype "passive"))
      (node (ref "C8") (pin "1") (pinfunction "1_1") (pintype "passive"))
      (node (ref "C9") (pin "-") (pinfunction "-_-") (pintype "passive"))
      (node (ref "J$1") (pin "GND@0") (pinfunction "GND_GND@0") (pintype "bidirectional"))
      (node (ref "J$1") (pin "GND@1") (pinfunction "GND_GND@1") (pintype "bidirectional"))
      (node (ref "J$1") (pin "GND@2") (pinfunction "GND_GND@2") (pintype "bidirectional"))
      (node (ref "J$1") (pin "GND@3") (pinfunction "GND_GND@3") (pintype "bidirectional"))
      (node (ref "J$2") (pin "GND@0") (pinfunction "GND_GND@0") (pintype "bidirectional"))
      (node (ref "J$2") (pin "GND@1") (pinfunction "GND_GND@1") (pintype "bidirectional"))
      (node (ref "J$2") (pin "GND@2") (pinfunction "GND_GND@2") (pintype "bidirectional"))
      (node (ref "J$2") (pin "GND@3") (pinfunction "GND_GND@3") (pintype "bidirectional"))
      (node (ref "J1") (pin "3") (pinfunction "GND_3") (pintype "bidirectional"))
      (node (ref "J1") (pin "5") (pinfunction "GND_5") (pintype "bidirectional"))
      (node (ref "J1") (pin "9") (pinfunction "GNDDTCT_9") (pintype "bidirectional"))
      (node (ref "J2") (pin "6") (pinfunction "6_6") (pintype "passive"))
      (node (ref "R16") (pin "1") (pinfunction "1_1") (pintype "passive"))
      (node (ref "R17") (pin "1") (pinfunction "1_1") (pintype "passive"))
      (node (ref "R20") (pin "1") (pinfunction "1_1") (pintype "passive"))
      (node (ref "R22") (pin "1") (pinfunction "1_1") (pintype "passive"))
      (node (ref "R3") (pin "1") (pinfunction "1_1") (pintype "passive"))
      (node (ref "R4") (pin "1") (pinfunction "1_1") (pintype "passive"))
      (node (ref "R6") (pin "1") (pinfunction "1_1") (pintype "passive"))
      (node (ref "R9") (pin "1") (pinfunction "1_1") (pintype "passive"))
      (node (ref "U$1") (pin "P14") (pinfunction "GND2_P14") (pintype "bidirectional"))
      (node (ref "U$1") (pin "P9") (pinfunction "GND_P9") (pintype "bidirectional"))
      (node (ref "U$3") (pin "10_GND") (pinfunction "10_GND_10_GND") (pintype "power_in"))
      (node (ref "U$3") (pin "12_GND") (pinfunction "12_GND_12_GND") (pintype "power_in"))
      (node (ref "U$3") (pin "1_GND") (pinfunction "1_GND_1_GND") (pintype "power_in"))
      (node (ref "U1") (pin "18") (pinfunction "GND1_18") (pintype "power_in"))
      (node (ref "U1") (pin "28") (pinfunction "GND2_28") (pintype "power_in"))
      (node (ref "U1") (pin "39") (pinfunction "GND3_39") (pintype "power_in"))
      (node (ref "U1") (pin "6") (pinfunction "GND_6") (pintype "power_in"))
      (node (ref "U2") (pin "11") (pinfunction "PAD_11") (pintype "power_in"))
      (node (ref "U2") (pin "12") (pinfunction "PAD_12") (pintype "power_in"))
      (node (ref "U2") (pin "13") (pinfunction "PAD_13") (pintype "power_in"))
      (node (ref "U2") (pin "14") (pinfunction "PAD_14") (pintype "power_in"))
      (node (ref "U2") (pin "15") (pinfunction "PAD_15") (pintype "power_in"))
      (node (ref "U2") (pin "4") (pinfunction "PGND_4") (pintype "power_in"))
      (node (ref "U2") (pin "9") (pinfunction "GND_9") (pintype "power_in"))
      (node (ref "U3") (pin "2") (pinfunction "GND_2_2") (pintype "passive"))
      (node (ref "U3") (pin "5") (pinfunction "GND_5") (pintype "passive"))
      (node (ref "U4") (pin "2") (pinfunction "GND_2") (pintype "passive"))
      (node (ref "U5") (pin "2") (pinfunction "GND_2") (pintype "passive"))
      (node (ref "U6") (pin "1") (pinfunction "GND_1") (pintype "power_in"))
      (node (ref "U6") (pin "10") (pinfunction "GND_10") (pintype "power_in"))
      (node (ref "U6") (pin "8") (pinfunction "GND_8") (pintype "power_in"))
      (node (ref "U7") (pin "4") (pinfunction "P4_4") (pintype "bidirectional"))
      (node (ref "U7") (pin "5") (pinfunction "OUT_5") (pintype "power_in"))
      (node (ref "X1") (pin "1") (pinfunction "1_1") (pintype "bidirectional"))
      (node (ref "X1") (pin "10") (pinfunction "10_10") (pintype "bidirectional"))
      (node (ref "Y1") (pin "2") (pinfunction "2_2") (pintype "passive"))
      (node (ref "Y3") (pin "2") (pinfunction "3_2") (pintype "passive"))
      (node (ref "Y3") (pin "4") (pinfunction "3_4") (pintype "passive"))
    )
    (net (code "31") (name "Net-(C11-+)") (class "Default")
      (node (ref "C11") (pin "1") (pinfunction "+_1") (pintype "passive"))
      (node (ref "C9") (pin "+") (pinfunction "+_+") (pintype "passive"))
      (node (ref "D2") (pin "C") (pinfunction "C_C") (pintype "passive"))
      (node (ref "U$3") (pin "6_V_BCKP") (pinfunction "6_V_BCKP_6_V_BCKP") (pintype "bidirectional"))
    )
    (net (code "32") (name "Net-(D1-PadC)") (class "Default")
      (node (ref "D1") (pin "C") (pinfunction "C_C") (pintype "passive"))
      (node (ref "R4") (pin "2") (pinfunction "2_2") (pintype "passive"))
    )
    (net (code "33") (name "Net-(D2-PadA)") (class "Default")
      (node (ref "D2") (pin "A") (pinfunction "A_A") (pintype "passive"))
      (node (ref "R5") (pin "2") (pinfunction "2_2") (pintype "passive"))
    )
    (net (code "34") (name "Net-(J$1-SIGNAL)") (class "Default")
      (node (ref "C17") (pin "2") (pinfunction "2_2") (pintype "passive"))
      (node (ref "J$1") (pin "SIG") (pinfunction "SIGNAL_SIG") (pintype "bidirectional"))
      (node (ref "U$1") (pin "P15") (pinfunction "LFANT_P15") (pintype "bidirectional"))
    )
    (net (code "35") (name "Net-(J$2-SIGNAL)") (class "Default")
      (node (ref "C20") (pin "1") (pinfunction "1_1") (pintype "passive"))
      (node (ref "J$2") (pin "SIG") (pinfunction "SIGNAL_SIG") (pintype "bidirectional"))
      (node (ref "U6") (pin "9") (pinfunction "ANT_9") (pintype "passive"))
    )
    (net (code "36") (name "Net-(J3-P$1)") (class "Default")
      (node (ref "C21") (pin "2") (pinfunction "2_2") (pintype "passive"))
      (node (ref "J3") (pin "1") (pinfunction "P$1_1") (pintype "bidirectional"))
      (node (ref "J4") (pin "1") (pinfunction "1_1") (pintype "passive"))
      (node (ref "R22") (pin "2") (pinfunction "2_2") (pintype "passive"))
      (node (ref "U7") (pin "2") (pinfunction "GND_2") (pintype "power_in"))
    )
    (net (code "37") (name "Net-(L2-Pad1)") (class "Default")
      (node (ref "L2") (pin "1") (pinfunction "1_1") (pintype "passive"))
      (node (ref "U$3") (pin "2_TXD1") (pinfunction "2_TXD1_2_TXD1") (pintype "bidirectional"))
    )
    (net (code "38") (name "Net-(L3-Pad1)") (class "Default")
      (node (ref "L3") (pin "1") (pinfunction "1_1") (pintype "passive"))
      (node (ref "U$3") (pin "3_RXD1") (pinfunction "3_RXD1_3_RXD1") (pintype "bidirectional"))
    )
    (net (code "39") (name "Net-(L4-Pad1)") (class "Default")
      (node (ref "L4") (pin "1") (pinfunction "1_1") (pintype "passive"))
      (node (ref "U$3") (pin "17_SCL2") (pinfunction "17_SCL2_17_SCL2") (pintype "bidirectional"))
    )
    (net (code "40") (name "Net-(L5-Pad1)") (class "Default")
      (node (ref "L5") (pin "1") (pinfunction "1_1") (pintype "passive"))
      (node (ref "U$3") (pin "16_SDA2") (pinfunction "16_SDA2_16_SDA2") (pintype "bidirectional"))
    )
    (net (code "41") (name "Net-(L6-2)") (class "Default")
      (node (ref "L6") (pin "P$2") (pinfunction "2_P$2") (pintype "passive"))
      (node (ref "U2") (pin "3") (pinfunction "L_3") (pintype "passive"))
    )
    (net (code "42") (name "Net-(U$2-SIGNAL)") (class "Default")
      (node (ref "R17") (pin "2") (pinfunction "2_2") (pintype "passive"))
      (node (ref "U$2") (pin "SIG") (pinfunction "SIGNAL_SIG") (pintype "bidirectional"))
      (node (ref "U$3") (pin "11_RF_IN") (pinfunction "11_RF_IN_11_RF_IN") (pintype "bidirectional"))
    )
    (net (code "43") (name "Net-(U1-(ADC3{slash}PCINT3)PA3)") (class "Default")
      (node (ref "D1") (pin "A") (pinfunction "A_A") (pintype "passive"))
      (node (ref "U1") (pin "34") (pinfunction "(ADC3/PCINT3)PA3_34") (pintype "bidirectional"))
    )
    (net (code "44") (name "Net-(U1-(ADC4{slash}PCINT4)PA4)") (class "Default")
      (node (ref "R2") (pin "1") (pinfunction "1_1") (pintype "passive"))
      (node (ref "R3") (pin "2") (pinfunction "2_2") (pintype "passive"))
      (node (ref "U1") (pin "33") (pinfunction "(ADC4/PCINT4)PA4_33") (pintype "bidirectional"))
    )
    (net (code "45") (name "Net-(U1-(ADC5{slash}PCINT5)PA5)") (class "Default")
      (node (ref "R15") (pin "1") (pinfunction "1_1") (pintype "passive"))
      (node (ref "R16") (pin "2") (pinfunction "2_2") (pintype "passive"))
      (node (ref "U1") (pin "32") (pinfunction "(ADC5/PCINT5)PA5_32") (pintype "bidirectional"))
    )
    (net (code "46") (name "Net-(U1-AVCC)") (class "Default")
      (node (ref "C4") (pin "1") (pinfunction "1_1") (pintype "passive"))
      (node (ref "L1") (pin "2") (pinfunction "2_2") (pintype "passive"))
      (node (ref "U1") (pin "27") (pinfunction "AVCC_27") (pintype "power_in"))
    )
    (net (code "47") (name "Net-(U1-XTAL1)") (class "Default")
      (node (ref "C15") (pin "1") (pinfunction "1_1") (pintype "passive"))
      (node (ref "TP1") (pin "TP") (pinfunction "TP_TP") (pintype "input"))
      (node (ref "U1") (pin "8") (pinfunction "XTAL1_8") (pintype "input"))
      (node (ref "Y1") (pin "3") (pinfunction "3_3") (pintype "passive"))
      (node (ref "Y3") (pin "3") (pinfunction "2_3") (pintype "passive"))
    )
    (net (code "48") (name "Net-(U1-XTAL2)") (class "Default")
      (node (ref "C16") (pin "1") (pinfunction "1_1") (pintype "passive"))
      (node (ref "U1") (pin "7") (pinfunction "XTAL2_7") (pintype "output"))
      (node (ref "Y1") (pin "1") (pinfunction "1_1") (pintype "passive"))
      (node (ref "Y3") (pin "1") (pinfunction "1_1") (pintype "passive"))
    )
    (net (code "49") (name "Net-(U2-FB)") (class "Default")
      (node (ref "R8") (pin "1") (pinfunction "1_1") (pintype "passive"))
      (node (ref "R9") (pin "2") (pinfunction "2_2") (pintype "passive"))
      (node (ref "U2") (pin "10") (pinfunction "FB_10") (pintype "passive"))
    )
    (net (code "50") (name "Net-(U2-PS)") (class "Default")
      (node (ref "R6") (pin "2") (pinfunction "2_2") (pintype "passive"))
      (node (ref "R7") (pin "1") (pinfunction "1_1") (pintype "passive"))
      (node (ref "U2") (pin "8") (pinfunction "PS_8") (pintype "input"))
    )
    (net (code "51") (name "Net-(U2-UVLO)") (class "Default")
      (node (ref "R19") (pin "1") (pinfunction "1_1") (pintype "passive"))
      (node (ref "R20") (pin "2") (pinfunction "2_2") (pintype "passive"))
      (node (ref "U2") (pin "7") (pinfunction "UVLO_7") (pintype "passive"))
    )
    (net (code "52") (name "Net-(U2-VAUX)") (class "Default")
      (node (ref "C12") (pin "2") (pinfunction "2_2") (pintype "passive"))
      (node (ref "U2") (pin "1") (pinfunction "VAUX_1") (pintype "passive"))
    )
    (net (code "53") (name "Net-(U7-EN)") (class "Default")
      (node (ref "C21") (pin "1") (pinfunction "1_1") (pintype "passive"))
      (node (ref "R21") (pin "1") (pinfunction "1_1") (pintype "passive"))
      (node (ref "U7") (pin "3") (pinfunction "EN_3") (pintype "input"))
    )
    (net (code "54") (name "VCC") (class "Default")
      (node (ref "C1") (pin "2") (pinfunction "2_2") (pintype "passive"))
      (node (ref "C13") (pin "2") (pinfunction "2_2") (pintype "passive"))
      (node (ref "C14") (pin "+") (pinfunction "+_+") (pintype "passive"))
      (node (ref "C2") (pin "2") (pinfunction "2_2") (pintype "passive"))
      (node (ref "C3") (pin "2") (pinfunction "2_2") (pintype "passive"))
      (node (ref "J1") (pin "1") (pinfunction "VCC_1") (pintype "bidirectional"))
      (node (ref "J2") (pin "2") (pinfunction "2_2") (pintype "passive"))
      (node (ref "L1") (pin "1") (pinfunction "1_1") (pintype "passive"))
      (node (ref "R1") (pin "1") (pinfunction "1_1") (pintype "passive"))
      (node (ref "R10") (pin "2") (pinfunction "2_2") (pintype "passive"))
      (node (ref "R11") (pin "2") (pinfunction "2_2") (pintype "passive"))
      (node (ref "R12") (pin "2") (pinfunction "2_2") (pintype "passive"))
      (node (ref "R18") (pin "1") (pinfunction "1_1") (pintype "passive"))
      (node (ref "R5") (pin "1") (pinfunction "1_1") (pintype "passive"))
      (node (ref "R8") (pin "2") (pinfunction "2_2") (pintype "passive"))
      (node (ref "U$1") (pin "P8") (pinfunction "VCC_P8") (pintype "bidirectional"))
      (node (ref "U1") (pin "17") (pinfunction "VCC1_17") (pintype "power_in"))
      (node (ref "U1") (pin "38") (pinfunction "VCC2_38") (pintype "power_in"))
      (node (ref "U1") (pin "5") (pinfunction "VCC_5") (pintype "power_in"))
      (node (ref "U2") (pin "2") (pinfunction "VOUT_2") (pintype "passive"))
      (node (ref "U3") (pin "4") (pinfunction "IN_4") (pintype "input"))
      (node (ref "U6") (pin "13") (pinfunction "3.3V_13") (pintype "power_in"))
      (node (ref "X1") (pin "6") (pinfunction "6_6") (pintype "bidirectional"))
    )
    (net (code "55") (name "unconnected-(J1-KEY-Pad7)") (class "Default")
      (node (ref "J1") (pin "7") (pinfunction "KEY_7") (pintype "bidirectional"))
    )
    (net (code "56") (name "unconnected-(NC1-P-Pad1)") (class "Default")
      (node (ref "NC1") (pin "1") (pinfunction "P_1") (pintype "passive"))
    )
    (net (code "57") (name "unconnected-(NC2-P-Pad1)") (class "Default")
      (node (ref "NC2") (pin "1") (pinfunction "P_1") (pintype "passive"))
    )
    (net (code "58") (name "unconnected-(U$1-DIO3-PadP5)") (class "Default")
      (node (ref "U$1") (pin "P5") (pinfunction "DIO3_P5") (pintype "bidirectional"))
    )
    (net (code "59") (name "unconnected-(U$1-DIO4-PadP6)") (class "Default")
      (node (ref "U$1") (pin "P6") (pinfunction "DIO4_P6") (pintype "bidirectional"))
    )
    (net (code "60") (name "unconnected-(U$3-Pad13_ANTON)") (class "Default")
      (node (ref "U$3") (pin "13_ANTON") (pinfunction "13_ANTON_13_ANTON") (pintype "bidirectional"))
    )
    (net (code "61") (name "unconnected-(U$3-Pad14_VCC_RF)") (class "Default")
      (node (ref "U$3") (pin "14_VCC_RF") (pinfunction "14_VCC_RF_14_VCC_RF") (pintype "bidirectional"))
    )
    (net (code "62") (name "unconnected-(U$3-Pad15_RESERVED)") (class "Default")
      (node (ref "U$3") (pin "15_RESERVED") (pinfunction "15_RESERVED_15_RESERVED") (pintype "bidirectional"))
    )
    (net (code "63") (name "unconnected-(U$3-Pad18_RESERVED)") (class "Default")
      (node (ref "U$3") (pin "18_RESERVED") (pinfunction "18_RESERVED_18_RESERVED") (pintype "bidirectional"))
    )
    (net (code "64") (name "unconnected-(U1-(ADC6{slash}PCINT6)PA6-Pad31)") (class "Default")
      (node (ref "U1") (pin "31") (pinfunction "(ADC6/PCINT6)PA6_31") (pintype "bidirectional"))
    )
    (net (code "65") (name "unconnected-(U1-(ADC7{slash}PCINT7)PA7-Pad30)") (class "Default")
      (node (ref "U1") (pin "30") (pinfunction "(ADC7/PCINT7)PA7_30") (pintype "bidirectional"))
    )
    (net (code "66") (name "unconnected-(U1-(AIN0{slash}INT2{slash}PCINT10)PB2-Pad42)") (class "Default")
      (node (ref "U1") (pin "42") (pinfunction "(AIN0/INT2/PCINT10)PB2_42") (pintype "bidirectional"))
    )
    (net (code "67") (name "unconnected-(U1-(AIN1{slash}OC0A{slash}PCINT11)PB3-Pad43)") (class "Default")
      (node (ref "U1") (pin "43") (pinfunction "(AIN1/OC0A/PCINT11)PB3_43") (pintype "bidirectional"))
    )
    (net (code "68") (name "unconnected-(U1-(T1{slash}CLKO{slash}PCINT9)PB1-Pad41)") (class "Default")
      (node (ref "U1") (pin "41") (pinfunction "(T1/CLKO/PCINT9)PB1_41") (pintype "bidirectional"))
    )
    (net (code "69") (name "unconnected-(U1-(TOSC1{slash}PCINT22)PC6-Pad25)") (class "Default")
      (node (ref "U1") (pin "25") (pinfunction "(TOSC1/PCINT22)PC6_25") (pintype "bidirectional"))
    )
    (net (code "70") (name "unconnected-(U1-(XCK0{slash}T0{slash}PCINT8)PB0-Pad40)") (class "Default")
      (node (ref "U1") (pin "40") (pinfunction "(XCK0/T0/PCINT8)PB0_40") (pintype "bidirectional"))
    )
    (net (code "71") (name "unconnected-(U3-N{slash}C-Pad6)") (class "Default")
      (node (ref "U3") (pin "6") (pinfunction "N/C_6") (pintype "no_connect"))
    )
    (net (code "72") (name "unconnected-(U4-NC-Pad4)") (class "Default")
      (node (ref "U4") (pin "4") (pinfunction "NC_4") (pintype "no_connect"))
    )
    (net (code "73") (name "unconnected-(U5-NC-Pad4)") (class "Default")
      (node (ref "U5") (pin "4") (pinfunction "NC_4") (pintype "no_connect"))
    )
    (net (code "74") (name "unconnected-(U6-DIO3-Pad11)") (class "Default")
      (node (ref "U6") (pin "11") (pinfunction "DIO3_11") (pintype "bidirectional"))
    )
    (net (code "75") (name "unconnected-(U6-DIO4-Pad12)") (class "Default")
      (node (ref "U6") (pin "12") (pinfunction "DIO4_12") (pintype "bidirectional"))
    )
  )
)
